# anet-esp8266-ext.net
KiCad netlist of a schematic drawn in EAGLE
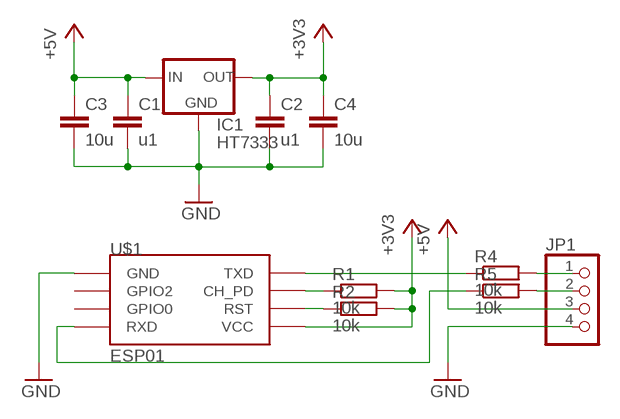
[diagram p0: schematic, sheet 1]

(export (version "E")
  (design (tool "Eeschema 10.0.6"))
  (components
    (comp (ref "C1")
      (value "u1")
      (footprint "eagle-import:C0805")
      (libsource (lib "eagle-import") (part "C-EUC0805"))
    )
    (comp (ref "C2")
      (value "u1")
      (footprint "eagle-import:C0805K")
      (libsource (lib "eagle-import") (part "C-EUC0805K"))
    )
    (comp (ref "C3")
      (value "10u")
      (footprint "eagle-import:C0805K")
      (libsource (lib "eagle-import") (part "C-EUC0805K"))
    )
    (comp (ref "C4")
      (value "10u")
      (footprint "eagle-import:C0805K")
      (libsource (lib "eagle-import") (part "C-EUC0805K"))
    )
    (comp (ref "IC1")
      (value "HT7333")
      (footprint "eagle-import:SOT-89")
      (libsource (lib "eagle-import") (part "HT7333"))
    )
    (comp (ref "JP1")
      (value "PINHD-1X4")
      (footprint "eagle-import:1X04")
      (libsource (lib "eagle-import") (part "PINHD-1X4"))
    )
    (comp (ref "R1")
      (value "10k")
      (footprint "eagle-import:M0805")
      (libsource (lib "eagle-import") (part "R-EU_M0805"))
    )
    (comp (ref "R2")
      (value "10k")
      (footprint "eagle-import:M0805")
      (libsource (lib "eagle-import") (part "R-EU_M0805"))
    )
    (comp (ref "R4")
      (value "10k")
      (footprint "eagle-import:R0805")
      (libsource (lib "eagle-import") (part "R-EU_R0805"))
    )
    (comp (ref "R5")
      (value "10k")
      (footprint "eagle-import:M0805")
      (libsource (lib "eagle-import") (part "R-EU_M0805"))
    )
    (comp (ref "U$1")
      (value "ESP01")
      (footprint "eagle-import:ESP01")
      (libsource (lib "eagle-import") (part "ESP01"))
    )
  )
  (nets
    (net (code "1") (name "+3V3") (class "Default")
      (node (ref "C2") (pin "1") (pinfunction "1_1") (pintype "passive"))
      (node (ref "C4") (pin "1") (pinfunction "1_1") (pintype "passive"))
      (node (ref "IC1") (pin "1") (pinfunction "OUT_1") (pintype "passive"))
      (node (ref "R1") (pin "2") (pinfunction "2_2") (pintype "passive"))
      (node (ref "R2") (pin "2") (pinfunction "2_2") (pintype "passive"))
      (node (ref "U$1") (pin "VCC") (pinfunction "VCC_VCC") (pintype "bidirectional"))
    )
    (net (code "2") (name "+5V") (class "Default")
      (node (ref "C1") (pin "1") (pinfunction "1_1") (pintype "passive"))
      (node (ref "C3") (pin "1") (pinfunction "1_1") (pintype "passive"))
      (node (ref "IC1") (pin "3") (pinfunction "IN_3") (pintype "input"))
      (node (ref "IC1") (pin "4") (pinfunction "IN_4") (pintype "input"))
      (node (ref "JP1") (pin "3") (pinfunction "3_3") (pintype "passive"))
    )
    (net (code "3") (name "GND") (class "Default")
      (node (ref "C1") (pin "2") (pinfunction "2_2") (pintype "passive"))
      (node (ref "C2") (pin "2") (pinfunction "2_2") (pintype "passive"))
      (node (ref "C3") (pin "2") (pinfunction "2_2") (pintype "passive"))
      (node (ref "C4") (pin "2") (pinfunction "2_2") (pintype "passive"))
      (node (ref "IC1") (pin "2") (pinfunction "GND_2") (pintype "input"))
      (node (ref "JP1") (pin "4") (pinfunction "4_4") (pintype "passive"))
      (node (ref "U$1") (pin "GND") (pinfunction "GND_GND") (pintype "bidirectional"))
    )
    (net (code "4") (name "Net-(JP1-Pad1)") (class "Default")
      (node (ref "JP1") (pin "1") (pinfunction "1_1") (pintype "passive"))
      (node (ref "R4") (pin "2") (pinfunction "2_2") (pintype "passive"))
    )
    (net (code "5") (name "Net-(JP1-Pad2)") (class "Default")
      (node (ref "JP1") (pin "2") (pinfunction "2_2") (pintype "passive"))
      (node (ref "R5") (pin "2") (pinfunction "2_2") (pintype "passive"))
    )
    (net (code "6") (name "Net-(R1-Pad1)") (class "Default")
      (node (ref "R1") (pin "1") (pinfunction "1_1") (pintype "passive"))
      (node (ref "U$1") (pin "CH_PD") (pinfunction "CH_PD_CH_PD") (pintype "bidirectional"))
    )
    (net (code "7") (name "Net-(R2-Pad1)") (class "Default")
      (node (ref "R2") (pin "1") (pinfunction "1_1") (pintype "passive"))
      (node (ref "U$1") (pin "RST") (pinfunction "RST_RST") (pintype "bidirectional"))
    )
    (net (code "8") (name "Net-(U$1-RXD)") (class "Default")
      (node (ref "R5") (pin "1") (pinfunction "1_1") (pintype "passive"))
      (node (ref "U$1") (pin "RX") (pinfunction "RXD_RX") (pintype "bidirectional"))
    )
    (net (code "9") (name "Net-(U$1-TXD)") (class "Default")
      (node (ref "R4") (pin "1") (pinfunction "1_1") (pintype "passive"))
      (node (ref "U$1") (pin "TX") (pinfunction "TXD_TX") (pintype "bidirectional"))
    )
    (net (code "10") (name "unconnected-(U$1-PadGPIO0)") (class "Default")
      (node (ref "U$1") (pin "GPIO0") (pinfunction "GPIO0_GPIO0") (pintype "bidirectional"))
    )
    (net (code "11") (name "unconnected-(U$1-PadGPIO2)") (class "Default")
      (node (ref "U$1") (pin "GPIO2") (pinfunction "GPIO2_GPIO2") (pintype "bidirectional"))
    )
  )
)
